# POW.net
KiCad netlist of a schematic drawn in Altium Designer
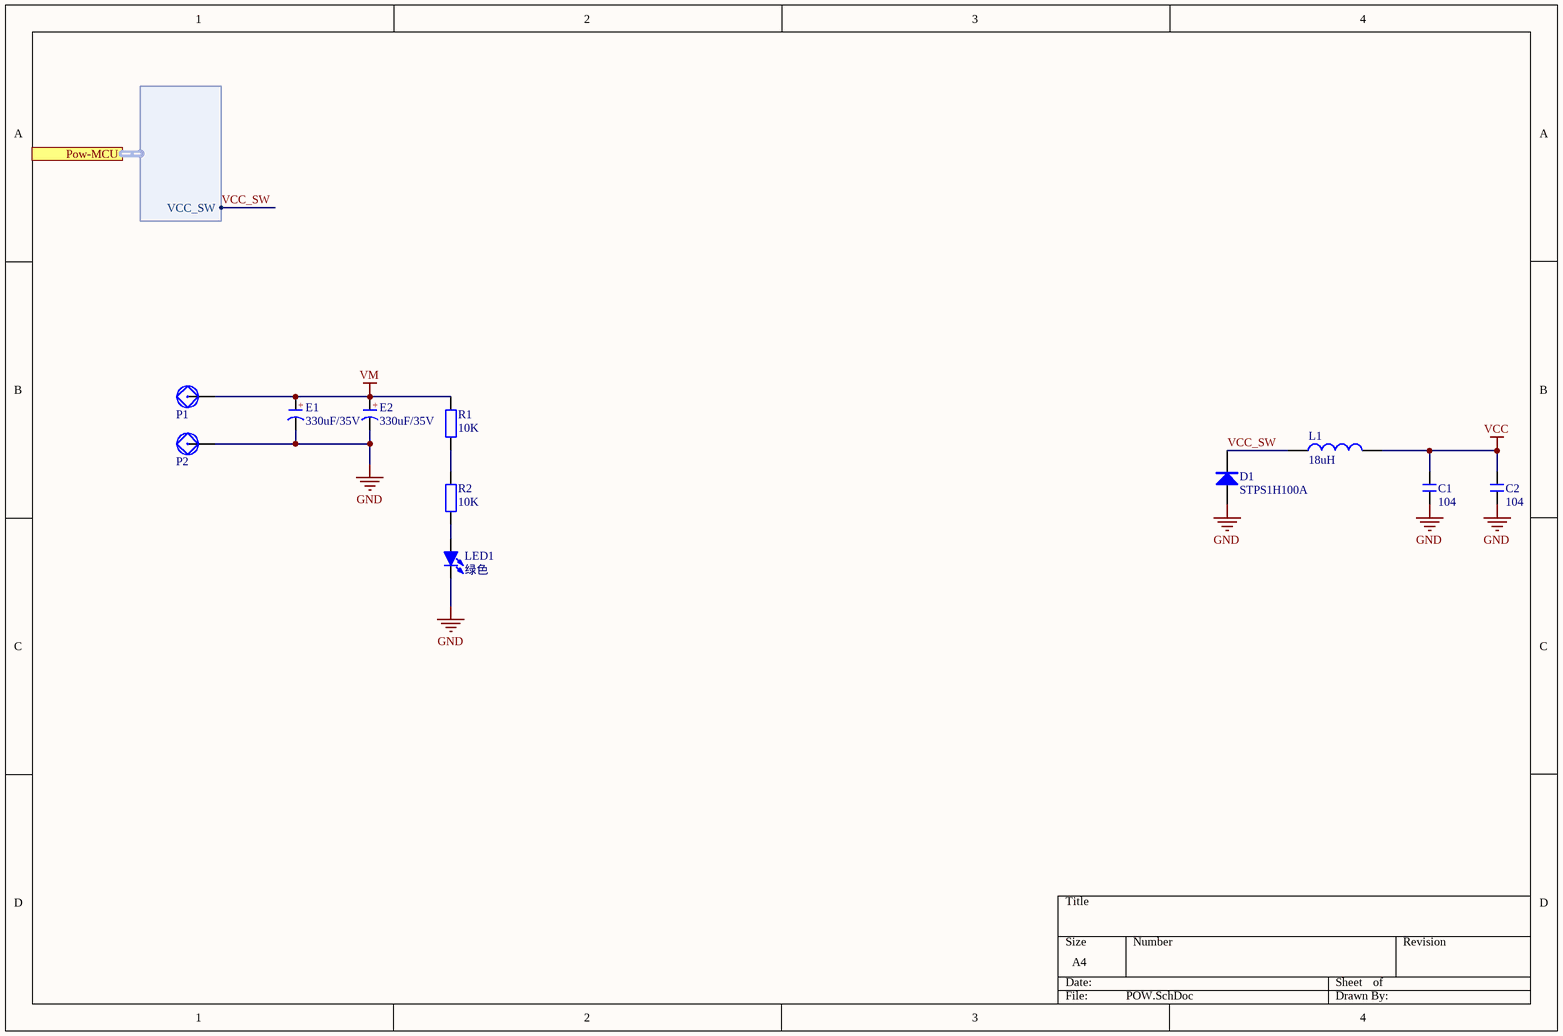
[diagram p0: POW.SchDoc]

(export (version "E")
  (design (tool "Eeschema 10.0.6"))
  (components
    (comp (ref "C1")
      (value "104")
      (footprint "C 0805_L")
      (description "无极性贴片电容")
      (fields (field (name "版权归属") "源创客"))
      (libsource (lib "3.1   - 电阻-电容-电感") (part "C"))
    )
    (comp (ref "C2")
      (value "104")
      (footprint "C 0805_L")
      (description "无极性贴片电容")
      (fields (field (name "版权归属") "源创客"))
      (libsource (lib "3.1   - 电阻-电容-电感") (part "C"))
    )
    (comp (ref "D1")
      (value "STPS1H100A")
      (footprint "SMA")
      (description "肖特基二极管")
      (fields (field (name "版权归属") "源创客"))
      (libsource (lib "8.1   - 二极管-整流桥") (part "SS14"))
    )
    (comp (ref "E1")
      (value "330uF/35V")
      (footprint "CAP 5.0*10*12.5")
      (description "直插电解电容")
      (fields (field (name "版权归属") "源创客"))
      (libsource (lib "3.1   - 电阻-电容-电感") (part "C-CAP"))
    )
    (comp (ref "E2")
      (value "330uF/35V")
      (footprint "CAP 5.0*10*12.5")
      (description "直插电解电容")
      (fields (field (name "版权归属") "源创客"))
      (libsource (lib "3.1   - 电阻-电容-电感") (part "C-CAP"))
    )
    (comp (ref "L1")
      (value "18uH")
      (footprint "L 0805")
      (description "小功率贴片电感")
      (fields (field (name "版权归属") "源创客"))
      (libsource (lib "3.1   - 电阻-电容-电感") (part "L"))
    )
    (comp (ref "LED1")
      (value "绿色")
      (footprint "LED 0603G")
      (description "贴片LED")
      (fields (field (name "版权归属") "源创客"))
      (libsource (lib "9.1   - LED") (part "LED-SMD"))
    )
    (comp (ref "P1")
      (value "功率焊盘")
      (footprint "功率焊盘")
      (libsource (lib "STSPIN32G4-Test-board") (part "功率焊盘"))
    )
    (comp (ref "P2")
      (value "功率焊盘")
      (footprint "功率焊盘")
      (libsource (lib "STSPIN32G4-Test-board") (part "功率焊盘"))
    )
    (comp (ref "R1")
      (value "10K")
      (footprint "R 0603_L")
      (description "贴片电阻")
      (fields (field (name "版权归属") "源创客"))
      (libsource (lib "3.1   - 电阻-电容-电感") (part "R"))
    )
    (comp (ref "R2")
      (value "10K")
      (footprint "R 0603_L")
      (description "贴片电阻")
      (fields (field (name "版权归属") "源创客"))
      (libsource (lib "3.1   - 电阻-电容-电感") (part "R"))
    )
  )
  (nets
    (net (code "2") (name "/VCC_SW") (class "Default")
      (node (ref "D1") (pin "2") (pinfunction "K_2") (pintype "passive"))
      (node (ref "L1") (pin "1") (pinfunction "1_1") (pintype "passive"))
    )
    (net (code "4") (name "GND") (class "Default")
      (node (ref "C1") (pin "1") (pinfunction "1_1") (pintype "passive"))
      (node (ref "C2") (pin "1") (pinfunction "1_1") (pintype "passive"))
      (node (ref "D1") (pin "1") (pinfunction "A_1") (pintype "passive"))
      (node (ref "E1") (pin "2") (pinfunction "K_2") (pintype "passive"))
      (node (ref "E2") (pin "2") (pinfunction "K_2") (pintype "passive"))
      (node (ref "LED1") (pin "2") (pinfunction "K_2") (pintype "passive"))
      (node (ref "P2") (pin "1") (pinfunction "1_1") (pintype "passive"))
    )
    (net (code "5") (name "Net-(LED1-A)") (class "Default")
      (node (ref "LED1") (pin "1") (pinfunction "A_1") (pintype "passive"))
      (node (ref "R2") (pin "1") (pinfunction "1_1") (pintype "passive"))
    )
    (net (code "6") (name "Net-(R1-Pad1)") (class "Default")
      (node (ref "R1") (pin "1") (pinfunction "1_1") (pintype "passive"))
      (node (ref "R2") (pin "2") (pinfunction "2_2") (pintype "passive"))
    )
    (net (code "7") (name "VCC") (class "Default")
      (node (ref "C1") (pin "2") (pinfunction "2_2") (pintype "passive"))
      (node (ref "C2") (pin "2") (pinfunction "2_2") (pintype "passive"))
      (node (ref "L1") (pin "2") (pinfunction "2_2") (pintype "passive"))
    )
    (net (code "8") (name "VM") (class "Default")
      (node (ref "E1") (pin "1") (pinfunction "A_1") (pintype "passive"))
      (node (ref "E2") (pin "1") (pinfunction "A_1") (pintype "passive"))
      (node (ref "P1") (pin "1") (pinfunction "1_1") (pintype "passive"))
      (node (ref "R1") (pin "2") (pinfunction "2_2") (pintype "passive"))
    )
  )
)
